# MCU.net
KiCad netlist of a schematic drawn in Altium Designer
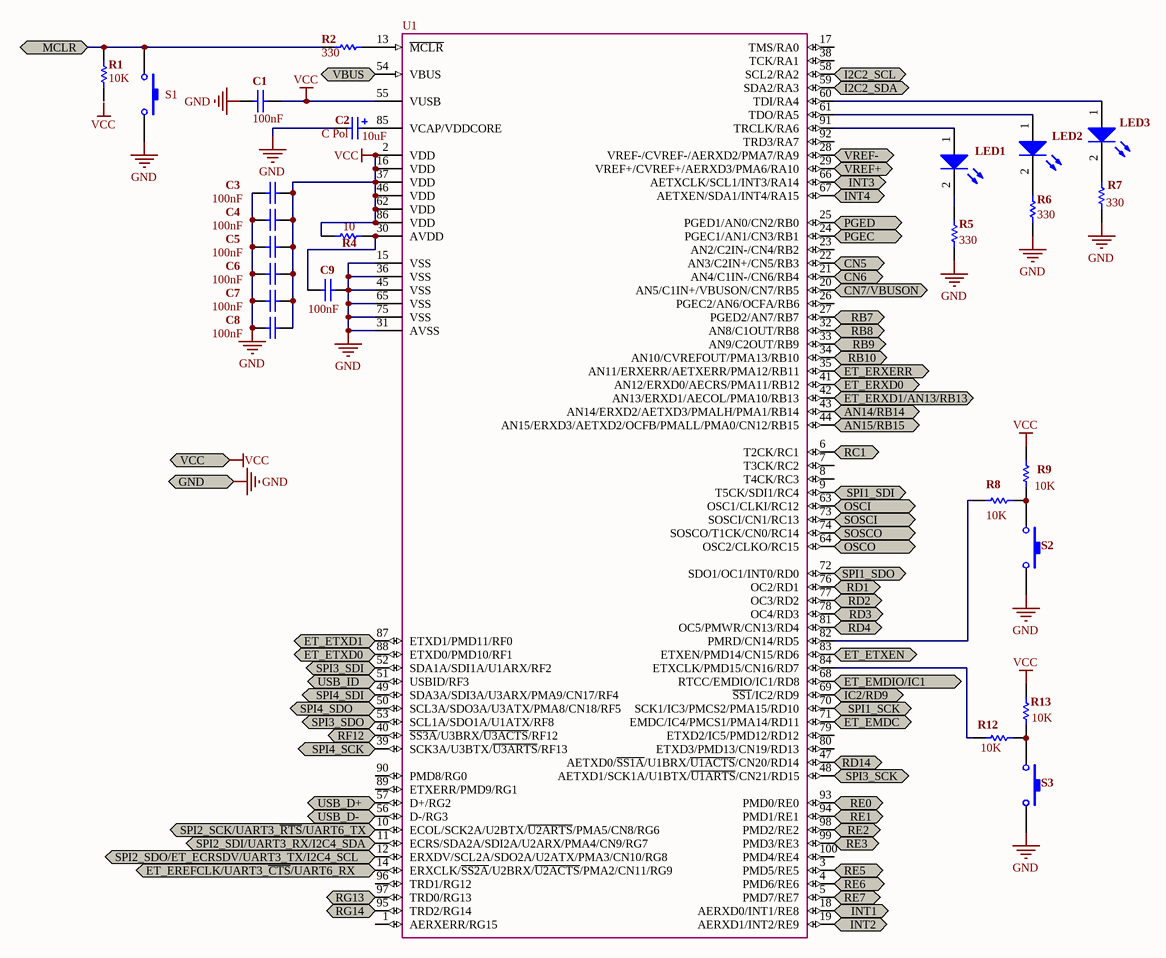
[diagram p0: MCU.SchDoc]

(export (version "E")
  (design (tool "Eeschema 10.0.6"))
  (components
    (comp (ref "C1")
      (value "100nF")
      (footprint "1608[0603]")
      (description "Capacitor")
      (fields (field (name "Comment") "Cap") (field (name "PUBLISHER") "Altium Limited"))
      (libsource (lib "Miscellaneous Devices") (part "Cap"))
    )
    (comp (ref "C2")
      (value "C Pol")
      (footprint "1206[3216]")
      (description "Polarized Capacitor (Surface Mount)")
      (fields
        (field (name "MANUFACTURER") "Generic Components")
        (field (name "ALTIUM_VALUE") "10uF")
        (field (name "PUBLISHER") "Altium Hobart Technology Centre")
      )
      (libsource (lib "LSI") (part "C Pol"))
    )
    (comp (ref "C3")
      (value "100nF")
      (footprint "1608[0603]")
      (description "Capacitor")
      (fields (field (name "Comment") "Cap") (field (name "PUBLISHER") "Altium Limited"))
      (libsource (lib "Miscellaneous Devices") (part "Cap"))
    )
    (comp (ref "C4")
      (value "100nF")
      (footprint "1608[0603]")
      (description "Capacitor")
      (fields (field (name "Comment") "Cap") (field (name "PUBLISHER") "Altium Limited"))
      (libsource (lib "Miscellaneous Devices") (part "Cap"))
    )
    (comp (ref "C5")
      (value "100nF")
      (footprint "1608[0603]")
      (description "Capacitor")
      (fields (field (name "Comment") "Cap") (field (name "PUBLISHER") "Altium Limited"))
      (libsource (lib "Miscellaneous Devices") (part "Cap"))
    )
    (comp (ref "C6")
      (value "100nF")
      (footprint "1608[0603]")
      (description "Capacitor")
      (fields (field (name "Comment") "Cap") (field (name "PUBLISHER") "Altium Limited"))
      (libsource (lib "Miscellaneous Devices") (part "Cap"))
    )
    (comp (ref "C7")
      (value "100nF")
      (footprint "1608[0603]")
      (description "Capacitor")
      (fields (field (name "Comment") "Cap") (field (name "PUBLISHER") "Altium Limited"))
      (libsource (lib "Miscellaneous Devices") (part "Cap"))
    )
    (comp (ref "C8")
      (value "100nF")
      (footprint "1608[0603]")
      (description "Capacitor")
      (fields (field (name "Comment") "Cap") (field (name "PUBLISHER") "Altium Limited"))
      (libsource (lib "Miscellaneous Devices") (part "Cap"))
    )
    (comp (ref "C9")
      (value "100nF")
      (footprint "1608[0603]")
      (description "Capacitor")
      (fields (field (name "Comment") "Cap") (field (name "PUBLISHER") "Altium Limited"))
      (libsource (lib "Miscellaneous Devices") (part "Cap"))
    )
    (comp (ref "LED1")
      (value "LED_SMD_Hg")
      (footprint "1608[0603]")
      (description "Typical BLUE SiC LED")
      (fields
        (field (name "MANUFACTURER") "Generic Components")
        (field (name "PUBLISHER") "Altium Hobart Technology Centre")
      )
      (libsource (lib "LSI") (part "LED_SMD_Hg"))
    )
    (comp (ref "LED2")
      (value "LED_SMD_Hg")
      (footprint "1608[0603]")
      (description "Typical BLUE SiC LED")
      (fields
        (field (name "MANUFACTURER") "Generic Components")
        (field (name "PUBLISHER") "Altium Hobart Technology Centre")
      )
      (libsource (lib "LSI") (part "LED_SMD_Hg"))
    )
    (comp (ref "LED3")
      (value "LED_SMD_Hg")
      (footprint "1608[0603]")
      (description "Typical BLUE SiC LED")
      (fields
        (field (name "MANUFACTURER") "Generic Components")
        (field (name "PUBLISHER") "Altium Hobart Technology Centre")
      )
      (libsource (lib "LSI") (part "LED_SMD_Hg"))
    )
    (comp (ref "R1")
      (value "10K")
      (footprint "1608[0603]")
      (description "Resistor")
      (fields
        (field (name "MANUFACTURER") "Generic Components")
        (field (name "Comment") "R")
        (field (name "PUBLISHER") "Altium Hobart Technology Centre")
      )
      (libsource (lib "LSI") (part "R"))
    )
    (comp (ref "R2")
      (value "330")
      (footprint "1608[0603]")
      (description "Resistor")
      (fields (field (name "Comment") "Res1") (field (name "PUBLISHER") "Altium Limited"))
      (libsource (lib "Miscellaneous Devices") (part "Res1"))
    )
    (comp (ref "R4")
      (value "10")
      (footprint "1608[0603]")
      (description "Resistor")
      (fields
        (field (name "MANUFACTURER") "Generic Components")
        (field (name "Comment") "R")
        (field (name "PUBLISHER") "Altium Hobart Technology Centre")
      )
      (libsource (lib "LSI") (part "R"))
    )
    (comp (ref "R5")
      (value "330")
      (footprint "1608[0603]")
      (description "Resistor")
      (fields
        (field (name "MANUFACTURER") "Generic Components")
        (field (name "Comment") "R")
        (field (name "PUBLISHER") "Altium Hobart Technology Centre")
      )
      (libsource (lib "LSI") (part "R"))
    )
    (comp (ref "R6")
      (value "330")
      (footprint "1608[0603]")
      (description "Resistor")
      (fields
        (field (name "MANUFACTURER") "Generic Components")
        (field (name "Comment") "R")
        (field (name "PUBLISHER") "Altium Hobart Technology Centre")
      )
      (libsource (lib "LSI") (part "R"))
    )
    (comp (ref "R7")
      (value "330")
      (footprint "1608[0603]")
      (description "Resistor")
      (fields
        (field (name "MANUFACTURER") "Generic Components")
        (field (name "Comment") "R")
        (field (name "PUBLISHER") "Altium Hobart Technology Centre")
      )
      (libsource (lib "LSI") (part "R"))
    )
    (comp (ref "R8")
      (value "10K")
      (footprint "1608[0603]")
      (description "Resistor")
      (fields
        (field (name "MANUFACTURER") "Generic Components")
        (field (name "Comment") "R")
        (field (name "PUBLISHER") "Altium Hobart Technology Centre")
      )
      (libsource (lib "LSI") (part "R"))
    )
    (comp (ref "R9")
      (value "10K")
      (footprint "1608[0603]")
      (description "Resistor")
      (fields
        (field (name "MANUFACTURER") "Generic Components")
        (field (name "Comment") "R")
        (field (name "PUBLISHER") "Altium Hobart Technology Centre")
      )
      (libsource (lib "LSI") (part "R"))
    )
    (comp (ref "R12")
      (value "10K")
      (footprint "1608[0603]")
      (description "Resistor")
      (fields
        (field (name "MANUFACTURER") "Generic Components")
        (field (name "Comment") "R")
        (field (name "PUBLISHER") "Altium Hobart Technology Centre")
      )
      (libsource (lib "LSI") (part "R"))
    )
    (comp (ref "R13")
      (value "10K")
      (footprint "1608[0603]")
      (description "Resistor")
      (fields
        (field (name "MANUFACTURER") "Generic Components")
        (field (name "Comment") "R")
        (field (name "PUBLISHER") "Altium Hobart Technology Centre")
      )
      (libsource (lib "LSI") (part "R"))
    )
    (comp (ref "s1_rst")
      (value "S1")
      (footprint "Pulsador")
      (description "Switch")
      (fields (field (name "MANUFACTURER") "Generic Components"))
      (libsource (lib "LSI") (part "Pulsador"))
    )
    (comp (ref "S2")
      (value "Pulsador")
      (footprint "Pulsador")
      (description "Switch")
      (fields (field (name "MANUFACTURER") "Generic Components"))
      (libsource (lib "LSI") (part "Pulsador"))
    )
    (comp (ref "S3")
      (value "Pulsador")
      (footprint "Pulsador")
      (description "Switch")
      (fields (field (name "MANUFACTURER") "Generic Components"))
      (libsource (lib "LSI") (part "Pulsador"))
    )
    (comp (ref "U1")
      (value "PIC32MX675F512L-80I/PT")
      (footprint "TQFP-PT100_N")
      (fields (field (name "PUBLISHER") "Altium Limited"))
      (libsource (lib "PlacaBase_agus") (part "PIC32MX675F512L-80I/PT"))
    )
  )
  (nets
    (net (code "1") (name "/AN14{slash}RB14") (class "Default")
      (node (ref "U1") (pin "43") (pinfunction "AN14/ERXD2/AETXD3/PMALH/PMA1/RB14_43") (pintype "bidirectional"))
    )
    (net (code "2") (name "/AN15{slash}RB15") (class "Default")
      (node (ref "U1") (pin "44") (pinfunction "AN15/ERXD3/AETXD2/OCFB/PMALL/PMA0/CN12/RB15_44") (pintype "bidirectional"))
    )
    (net (code "3") (name "/CN5") (class "Default")
      (node (ref "U1") (pin "22") (pinfunction "AN3/C2IN+/CN5/RB3_22") (pintype "bidirectional"))
    )
    (net (code "4") (name "/CN6") (class "Default")
      (node (ref "U1") (pin "21") (pinfunction "AN4/C1IN-/CN6/RB4_21") (pintype "bidirectional"))
    )
    (net (code "5") (name "/CN7{slash}VBUSON") (class "Default")
      (node (ref "U1") (pin "20") (pinfunction "AN5/C1IN+/VBUSON/CN7/RB5_20") (pintype "bidirectional"))
    )
    (net (code "6") (name "/ET_EMDC") (class "Default")
      (node (ref "U1") (pin "71") (pinfunction "EMDC/IC4/PMCS1/PMA14/RD11_71") (pintype "bidirectional"))
    )
    (net (code "7") (name "/ET_EMDIO{slash}IC1") (class "Default")
      (node (ref "U1") (pin "68") (pinfunction "RTCC/EMDIO/IC1/RD8_68") (pintype "bidirectional"))
    )
    (net (code "8") (name "/ET_EREFCLK{slash}UART3_~{CTS}{slash}UART6_RX") (class "Default")
      (node (ref "U1") (pin "14") (pinfunction "ERXCLK/~{SS2A}/U2BRX/~{U2ACTS}/PMA2/CN11/RG9_14") (pintype "bidirectional"))
    )
    (net (code "9") (name "/ET_ERXD0") (class "Default")
      (node (ref "U1") (pin "41") (pinfunction "AN12/ERXD0/AECRS/PMA11/RB12_41") (pintype "bidirectional"))
    )
    (net (code "10") (name "/ET_ERXD1{slash}AN13{slash}RB13") (class "Default")
      (node (ref "U1") (pin "42") (pinfunction "AN13/ERXD1/AECOL/PMA10/RB13_42") (pintype "bidirectional"))
    )
    (net (code "11") (name "/ET_ERXERR") (class "Default")
      (node (ref "U1") (pin "35") (pinfunction "AN11/ERXERR/AETXERR/PMA12/RB11_35") (pintype "bidirectional"))
    )
    (net (code "12") (name "/ET_ETXD0") (class "Default")
      (node (ref "U1") (pin "88") (pinfunction "ETXD0/PMD10/RF1_88") (pintype "bidirectional"))
    )
    (net (code "13") (name "/ET_ETXD1") (class "Default")
      (node (ref "U1") (pin "87") (pinfunction "ETXD1/PMD11/RF0_87") (pintype "bidirectional"))
    )
    (net (code "14") (name "/ET_ETXEN") (class "Default")
      (node (ref "U1") (pin "83") (pinfunction "ETXEN/PMD14/CN15/RD6_83") (pintype "bidirectional"))
    )
    (net (code "15") (name "/I2C2_SCL") (class "Default")
      (node (ref "U1") (pin "58") (pinfunction "SCL2/RA2_58") (pintype "bidirectional"))
    )
    (net (code "16") (name "/I2C2_SDA") (class "Default")
      (node (ref "U1") (pin "59") (pinfunction "SDA2/RA3_59") (pintype "bidirectional"))
    )
    (net (code "17") (name "/IC2{slash}RD9") (class "Default")
      (node (ref "U1") (pin "69") (pinfunction "~{SS1}/IC2/RD9_69") (pintype "bidirectional"))
    )
    (net (code "18") (name "/INT1") (class "Default")
      (node (ref "U1") (pin "18") (pinfunction "AERXD0/INT1/RE8_18") (pintype "bidirectional"))
    )
    (net (code "19") (name "/INT2") (class "Default")
      (node (ref "U1") (pin "19") (pinfunction "AERXD1/INT2/RE9_19") (pintype "bidirectional"))
    )
    (net (code "20") (name "/INT3") (class "Default")
      (node (ref "U1") (pin "66") (pinfunction "AETXCLK/SCL1/INT3/RA14_66") (pintype "bidirectional"))
    )
    (net (code "21") (name "/INT4") (class "Default")
      (node (ref "U1") (pin "67") (pinfunction "AETXEN/SDA1/INT4/RA15_67") (pintype "bidirectional"))
    )
    (net (code "22") (name "/MCLR") (class "Default")
      (node (ref "R1") (pin "1") (pinfunction "1_1") (pintype "passive"))
      (node (ref "R2") (pin "1") (pinfunction "1_1") (pintype "passive"))
      (node (ref "s1_rst") (pin "1") (pinfunction "1_1") (pintype "passive"))
    )
    (net (code "23") (name "/OSCI") (class "Default")
      (node (ref "U1") (pin "63") (pinfunction "OSC1/CLKI/RC12_63") (pintype "bidirectional"))
    )
    (net (code "24") (name "/OSCO") (class "Default")
      (node (ref "U1") (pin "64") (pinfunction "OSC2/CLKO/RC15_64") (pintype "bidirectional"))
    )
    (net (code "25") (name "/PGEC") (class "Default")
      (node (ref "U1") (pin "24") (pinfunction "PGEC1/AN1/CN3/RB1_24") (pintype "bidirectional"))
    )
    (net (code "26") (name "/PGED") (class "Default")
      (node (ref "U1") (pin "25") (pinfunction "PGED1/AN0/CN2/RB0_25") (pintype "bidirectional"))
    )
    (net (code "27") (name "/RB7") (class "Default")
      (node (ref "U1") (pin "27") (pinfunction "PGED2/AN7/RB7_27") (pintype "bidirectional"))
    )
    (net (code "28") (name "/RB8") (class "Default")
      (node (ref "U1") (pin "32") (pinfunction "AN8/C1OUT/RB8_32") (pintype "bidirectional"))
    )
    (net (code "29") (name "/RB9") (class "Default")
      (node (ref "U1") (pin "33") (pinfunction "AN9/C2OUT/RB9_33") (pintype "bidirectional"))
    )
    (net (code "30") (name "/RB10") (class "Default")
      (node (ref "U1") (pin "34") (pinfunction "AN10/CVREFOUT/PMA13/RB10_34") (pintype "bidirectional"))
    )
    (net (code "31") (name "/RC1") (class "Default")
      (node (ref "U1") (pin "6") (pinfunction "T2CK/RC1_6") (pintype "bidirectional"))
    )
    (net (code "32") (name "/RD1") (class "Default")
      (node (ref "U1") (pin "76") (pinfunction "OC2/RD1_76") (pintype "bidirectional"))
    )
    (net (code "33") (name "/RD2") (class "Default")
      (node (ref "U1") (pin "77") (pinfunction "OC3/RD2_77") (pintype "bidirectional"))
    )
    (net (code "34") (name "/RD3") (class "Default")
      (node (ref "U1") (pin "78") (pinfunction "OC4/RD3_78") (pintype "bidirectional"))
    )
    (net (code "35") (name "/RD4") (class "Default")
      (node (ref "U1") (pin "81") (pinfunction "OC5/PMWR/CN13/RD4_81") (pintype "bidirectional"))
    )
    (net (code "36") (name "/RD14") (class "Default")
      (node (ref "U1") (pin "47") (pinfunction "AETXD0/~{SS1A}/U1BRX/~{U1ACTS}/CN20/RD14_47") (pintype "bidirectional"))
    )
    (net (code "37") (name "/RE0") (class "Default")
      (node (ref "U1") (pin "93") (pinfunction "PMD0/RE0_93") (pintype "bidirectional"))
    )
    (net (code "38") (name "/RE1") (class "Default")
      (node (ref "U1") (pin "94") (pinfunction "PMD1/RE1_94") (pintype "bidirectional"))
    )
    (net (code "39") (name "/RE2") (class "Default")
      (node (ref "U1") (pin "98") (pinfunction "PMD2/RE2_98") (pintype "bidirectional"))
    )
    (net (code "40") (name "/RE3") (class "Default")
      (node (ref "U1") (pin "99") (pinfunction "PMD3/RE3_99") (pintype "bidirectional"))
    )
    (net (code "41") (name "/RE5") (class "Default")
      (node (ref "U1") (pin "3") (pinfunction "PMD5/RE5_3") (pintype "bidirectional"))
    )
    (net (code "42") (name "/RE6") (class "Default")
      (node (ref "U1") (pin "4") (pinfunction "PMD6/RE6_4") (pintype "bidirectional"))
    )
    (net (code "43") (name "/RE7") (class "Default")
      (node (ref "U1") (pin "5") (pinfunction "PMD7/RE7_5") (pintype "bidirectional"))
    )
    (net (code "44") (name "/RF12") (class "Default")
      (node (ref "U1") (pin "40") (pinfunction "~{SS3A}/U3BRX/~{U3ACTS}/RF12_40") (pintype "bidirectional"))
    )
    (net (code "45") (name "/RG13") (class "Default")
      (node (ref "U1") (pin "97") (pinfunction "TRD0/RG13_97") (pintype "bidirectional"))
    )
    (net (code "46") (name "/RG14") (class "Default")
      (node (ref "U1") (pin "95") (pinfunction "TRD2/RG14_95") (pintype "bidirectional"))
    )
    (net (code "47") (name "/SOSCI") (class "Default")
      (node (ref "U1") (pin "73") (pinfunction "SOSCI/CN1/RC13_73") (pintype "bidirectional"))
    )
    (net (code "48") (name "/SOSCO") (class "Default")
      (node (ref "U1") (pin "74") (pinfunction "SOSCO/T1CK/CN0/RC14_74") (pintype "bidirectional"))
    )
    (net (code "49") (name "/SPI1_SCK") (class "Default")
      (node (ref "U1") (pin "70") (pinfunction "SCK1/IC3/PMCS2/PMA15/RD10_70") (pintype "bidirectional"))
    )
    (net (code "50") (name "/SPI1_SDI") (class "Default")
      (node (ref "U1") (pin "9") (pinfunction "T5CK/SDI1/RC4_9") (pintype "bidirectional"))
    )
    (net (code "51") (name "/SPI1_SDO") (class "Default")
      (node (ref "U1") (pin "72") (pinfunction "SDO1/OC1/INT0/RD0_72") (pintype "bidirectional"))
    )
    (net (code "52") (name "/SPI2_SCK{slash}UART3_~{RTS}{slash}UART6_TX") (class "Default")
      (node (ref "U1") (pin "10") (pinfunction "ECOL/SCK2A/U2BTX/~{U2ARTS}/PMA5/CN8/RG6_10") (pintype "bidirectional"))
    )
    (net (code "53") (name "/SPI2_SDI{slash}UART3_RX{slash}I2C4_SDA") (class "Default")
      (node (ref "U1") (pin "11") (pinfunction "ECRS/SDA2A/SDI2A/U2ARX/PMA4/CN9/RG7_11") (pintype "bidirectional"))
    )
    (net (code "54") (name "/SPI2_SDO{slash}ET_ECRSDV{slash}UART3_TX{slash}I2C4_SCL") (class "Default")
      (node (ref "U1") (pin "12") (pinfunction "ERXDV/SCL2A/SDO2A/U2ATX/PMA3/CN10/RG8_12") (pintype "bidirectional"))
    )
    (net (code "55") (name "/SPI3_SCK") (class "Default")
      (node (ref "U1") (pin "48") (pinfunction "AETXD1/SCK1A/U1BTX/~{U1ARTS}/CN21/RD15_48") (pintype "bidirectional"))
    )
    (net (code "56") (name "/SPI3_SDI") (class "Default")
      (node (ref "U1") (pin "52") (pinfunction "SDA1A/SDI1A/U1ARX/RF2_52") (pintype "bidirectional"))
    )
    (net (code "57") (name "/SPI3_SDO") (class "Default")
      (node (ref "U1") (pin "53") (pinfunction "SCL1A/SDO1A/U1ATX/RF8_53") (pintype "bidirectional"))
    )
    (net (code "58") (name "/SPI4_SCK") (class "Default")
      (node (ref "U1") (pin "39") (pinfunction "SCK3A/U3BTX/~{U3ARTS}/RF13_39") (pintype "bidirectional"))
    )
    (net (code "59") (name "/SPI4_SDI") (class "Default")
      (node (ref "U1") (pin "49") (pinfunction "SDA3A/SDI3A/U3ARX/PMA9/CN17/RF4_49") (pintype "bidirectional"))
    )
    (net (code "60") (name "/SPI4_SDO") (class "Default")
      (node (ref "U1") (pin "50") (pinfunction "SCL3A/SDO3A/U3ATX/PMA8/CN18/RF5_50") (pintype "bidirectional"))
    )
    (net (code "61") (name "/USB_D+") (class "Default")
      (node (ref "U1") (pin "57") (pinfunction "D+/RG2_57") (pintype "bidirectional"))
    )
    (net (code "62") (name "/USB_D-") (class "Default")
      (node (ref "U1") (pin "56") (pinfunction "D-/RG3_56") (pintype "bidirectional"))
    )
    (net (code "63") (name "/USB_ID") (class "Default")
      (node (ref "U1") (pin "51") (pinfunction "USBID/RF3_51") (pintype "bidirectional"))
    )
    (net (code "64") (name "/VBUS") (class "Default")
      (node (ref "U1") (pin "54") (pinfunction "VBUS_54") (pintype "input"))
    )
    (net (code "65") (name "/VREF+") (class "Default")
      (node (ref "U1") (pin "29") (pinfunction "VREF+/CVREF+/AERXD3/PMA6/RA10_29") (pintype "bidirectional"))
    )
    (net (code "66") (name "/VREF-") (class "Default")
      (node (ref "U1") (pin "28") (pinfunction "VREF-/CVREF-/AERXD2/PMA7/RA9_28") (pintype "bidirectional"))
    )
    (net (code "67") (name "GND") (class "Default")
      (node (ref "C1") (pin "2") (pinfunction "2_2") (pintype "passive"))
      (node (ref "C2") (pin "2") (pinfunction "2_2") (pintype "passive"))
      (node (ref "C3") (pin "1") (pinfunction "1_1") (pintype "passive"))
      (node (ref "C4") (pin "1") (pinfunction "1_1") (pintype "passive"))
      (node (ref "C5") (pin "1") (pinfunction "1_1") (pintype "passive"))
      (node (ref "C6") (pin "1") (pinfunction "1_1") (pintype "passive"))
      (node (ref "C7") (pin "1") (pinfunction "1_1") (pintype "passive"))
      (node (ref "C8") (pin "1") (pinfunction "1_1") (pintype "passive"))
      (node (ref "C9") (pin "1") (pinfunction "1_1") (pintype "passive"))
      (node (ref "R5") (pin "1") (pinfunction "1_1") (pintype "passive"))
      (node (ref "R6") (pin "1") (pinfunction "1_1") (pintype "passive"))
      (node (ref "R7") (pin "1") (pinfunction "1_1") (pintype "passive"))
      (node (ref "S2") (pin "2") (pinfunction "2_2") (pintype "passive"))
      (node (ref "S3") (pin "2") (pinfunction "2_2") (pintype "passive"))
      (node (ref "U1") (pin "15") (pinfunction "VSS_15") (pintype "power_in"))
      (node (ref "U1") (pin "31") (pinfunction "AVSS_31") (pintype "power_in"))
      (node (ref "U1") (pin "36") (pinfunction "VSS_36") (pintype "power_in"))
      (node (ref "U1") (pin "45") (pinfunction "VSS_45") (pintype "power_in"))
      (node (ref "U1") (pin "65") (pinfunction "VSS_65") (pintype "power_in"))
      (node (ref "U1") (pin "75") (pinfunction "VSS_75") (pintype "power_in"))
      (node (ref "s1_rst") (pin "2") (pinfunction "2_2") (pintype "passive"))
    )
    (net (code "68") (name "Net-(LED1-A)") (class "Default")
      (node (ref "LED1") (pin "1") (pinfunction "A_1") (pintype "passive"))
      (node (ref "U1") (pin "91") (pinfunction "TRCLK/RA6_91") (pintype "bidirectional"))
    )
    (net (code "69") (name "Net-(LED1-K)") (class "Default")
      (node (ref "LED1") (pin "2") (pinfunction "K_2") (pintype "passive"))
      (node (ref "R5") (pin "2") (pinfunction "2_2") (pintype "passive"))
    )
    (net (code "70") (name "Net-(LED2-A)") (class "Default")
      (node (ref "LED2") (pin "1") (pinfunction "A_1") (pintype "passive"))
      (node (ref "U1") (pin "61") (pinfunction "TDO/RA5_61") (pintype "bidirectional"))
    )
    (net (code "71") (name "Net-(LED2-K)") (class "Default")
      (node (ref "LED2") (pin "2") (pinfunction "K_2") (pintype "passive"))
      (node (ref "R6") (pin "2") (pinfunction "2_2") (pintype "passive"))
    )
    (net (code "72") (name "Net-(LED3-A)") (class "Default")
      (node (ref "LED3") (pin "1") (pinfunction "A_1") (pintype "passive"))
      (node (ref "U1") (pin "60") (pinfunction "TDI/RA4_60") (pintype "bidirectional"))
    )
    (net (code "73") (name "Net-(LED3-K)") (class "Default")
      (node (ref "LED3") (pin "2") (pinfunction "K_2") (pintype "passive"))
      (node (ref "R7") (pin "2") (pinfunction "2_2") (pintype "passive"))
    )
    (net (code "74") (name "Net-(R8-Pad1)") (class "Default")
      (node (ref "R8") (pin "1") (pinfunction "1_1") (pintype "passive"))
      (node (ref "R9") (pin "1") (pinfunction "1_1") (pintype "passive"))
      (node (ref "S2") (pin "1") (pinfunction "1_1") (pintype "passive"))
    )
    (net (code "75") (name "Net-(R12-Pad1)") (class "Default")
      (node (ref "R12") (pin "1") (pinfunction "1_1") (pintype "passive"))
      (node (ref "R13") (pin "1") (pinfunction "1_1") (pintype "passive"))
      (node (ref "S3") (pin "1") (pinfunction "1_1") (pintype "passive"))
    )
    (net (code "76") (name "Net-(U1-AVDD)") (class "Default")
      (node (ref "C9") (pin "2") (pinfunction "2_2") (pintype "passive"))
      (node (ref "R4") (pin "1") (pinfunction "1_1") (pintype "passive"))
      (node (ref "U1") (pin "30") (pinfunction "AVDD_30") (pintype "power_in"))
    )
    (net (code "77") (name "Net-(U1-ETXCLK{slash}PMD15{slash}CN16{slash}RD7)") (class "Default")
      (node (ref "R12") (pin "2") (pinfunction "2_2") (pintype "passive"))
      (node (ref "U1") (pin "84") (pinfunction "ETXCLK/PMD15/CN16/RD7_84") (pintype "bidirectional"))
    )
    (net (code "78") (name "Net-(U1-PMRD{slash}CN14{slash}RD5)") (class "Default")
      (node (ref "R8") (pin "2") (pinfunction "2_2") (pintype "passive"))
      (node (ref "U1") (pin "82") (pinfunction "PMRD/CN14/RD5_82") (pintype "bidirectional"))
    )
    (net (code "79") (name "Net-(U1-VCAP{slash}VDDCORE)") (class "Default")
      (node (ref "C2") (pin "1") (pinfunction "1_1") (pintype "passive"))
      (node (ref "U1") (pin "85") (pinfunction "VCAP/VDDCORE_85") (pintype "power_in"))
    )
    (net (code "80") (name "Net-(U1-~{MCLR})") (class "Default")
      (node (ref "R2") (pin "2") (pinfunction "2_2") (pintype "passive"))
      (node (ref "U1") (pin "13") (pinfunction "~{MCLR}_13") (pintype "input"))
    )
    (net (code "81") (name "VCC") (class "Default")
      (node (ref "C1") (pin "1") (pinfunction "1_1") (pintype "passive"))
      (node (ref "C3") (pin "2") (pinfunction "2_2") (pintype "passive"))
      (node (ref "C4") (pin "2") (pinfunction "2_2") (pintype "passive"))
      (node (ref "C5") (pin "2") (pinfunction "2_2") (pintype "passive"))
      (node (ref "C6") (pin "2") (pinfunction "2_2") (pintype "passive"))
      (node (ref "C7") (pin "2") (pinfunction "2_2") (pintype "passive"))
      (node (ref "C8") (pin "2") (pinfunction "2_2") (pintype "passive"))
      (node (ref "R13") (pin "2") (pinfunction "2_2") (pintype "passive"))
      (node (ref "R4") (pin "2") (pinfunction "2_2") (pintype "passive"))
      (node (ref "R9") (pin "2") (pinfunction "2_2") (pintype "passive"))
      (node (ref "U1") (pin "16") (pinfunction "VDD_16") (pintype "power_in"))
      (node (ref "U1") (pin "2") (pinfunction "VDD_2") (pintype "power_in"))
      (node (ref "U1") (pin "37") (pinfunction "VDD_37") (pintype "power_in"))
      (node (ref "U1") (pin "46") (pinfunction "VDD_46") (pintype "power_in"))
      (node (ref "U1") (pin "55") (pinfunction "VUSB_55") (pintype "power_in"))
      (node (ref "U1") (pin "62") (pinfunction "VDD_62") (pintype "power_in"))
      (node (ref "U1") (pin "86") (pinfunction "VDD_86") (pintype "power_in"))
    )
    (net (code "82") (name "unconnected-(R1-Pad2)") (class "Default")
      (node (ref "R1") (pin "2") (pinfunction "2_2") (pintype "passive"))
    )
    (net (code "83") (name "unconnected-(U1-AERXERR{slash}RG15-Pad1)") (class "Default")
      (node (ref "U1") (pin "1") (pinfunction "AERXERR/RG15_1") (pintype "bidirectional"))
    )
    (net (code "84") (name "unconnected-(U1-AN2{slash}C2IN-{slash}CN4{slash}RB2-Pad23)") (class "Default")
      (node (ref "U1") (pin "23") (pinfunction "AN2/C2IN-/CN4/RB2_23") (pintype "bidirectional"))
    )
    (net (code "85") (name "unconnected-(U1-ETXD2{slash}IC5{slash}PMD12{slash}RD12-Pad79)") (class "Default")
      (node (ref "U1") (pin "79") (pinfunction "ETXD2/IC5/PMD12/RD12_79") (pintype "bidirectional"))
    )
    (net (code "86") (name "unconnected-(U1-ETXD3{slash}PMD13{slash}CN19{slash}RD13-Pad80)") (class "Default")
      (node (ref "U1") (pin "80") (pinfunction "ETXD3/PMD13/CN19/RD13_80") (pintype "bidirectional"))
    )
    (net (code "87") (name "unconnected-(U1-ETXERR{slash}PMD9{slash}RG1-Pad89)") (class "Default")
      (node (ref "U1") (pin "89") (pinfunction "ETXERR/PMD9/RG1_89") (pintype "bidirectional"))
    )
    (net (code "88") (name "unconnected-(U1-PGEC2{slash}AN6{slash}OCFA{slash}RB6-Pad26)") (class "Default")
      (node (ref "U1") (pin "26") (pinfunction "PGEC2/AN6/OCFA/RB6_26") (pintype "bidirectional"))
    )
    (net (code "89") (name "unconnected-(U1-PMD4{slash}RE4-Pad100)") (class "Default")
      (node (ref "U1") (pin "100") (pinfunction "PMD4/RE4_100") (pintype "bidirectional"))
    )
    (net (code "90") (name "unconnected-(U1-PMD8{slash}RG0-Pad90)") (class "Default")
      (node (ref "U1") (pin "90") (pinfunction "PMD8/RG0_90") (pintype "bidirectional"))
    )
    (net (code "91") (name "unconnected-(U1-T3CK{slash}RC2-Pad7)") (class "Default")
      (node (ref "U1") (pin "7") (pinfunction "T3CK/RC2_7") (pintype "bidirectional"))
    )
    (net (code "92") (name "unconnected-(U1-T4CK{slash}RC3-Pad8)") (class "Default")
      (node (ref "U1") (pin "8") (pinfunction "T4CK/RC3_8") (pintype "bidirectional"))
    )
    (net (code "93") (name "unconnected-(U1-TCK{slash}RA1-Pad38)") (class "Default")
      (node (ref "U1") (pin "38") (pinfunction "TCK/RA1_38") (pintype "bidirectional"))
    )
    (net (code "94") (name "unconnected-(U1-TMS{slash}RA0-Pad17)") (class "Default")
      (node (ref "U1") (pin "17") (pinfunction "TMS/RA0_17") (pintype "bidirectional"))
    )
    (net (code "95") (name "unconnected-(U1-TRD1{slash}RG12-Pad96)") (class "Default")
      (node (ref "U1") (pin "96") (pinfunction "TRD1/RG12_96") (pintype "bidirectional"))
    )
    (net (code "96") (name "unconnected-(U1-TRD3{slash}RA7-Pad92)") (class "Default")
      (node (ref "U1") (pin "92") (pinfunction "TRD3/RA7_92") (pintype "bidirectional"))
    )
  )
)
